# DACWaveyRadar.net
KiCad netlist of a schematic drawn in Altium Designer
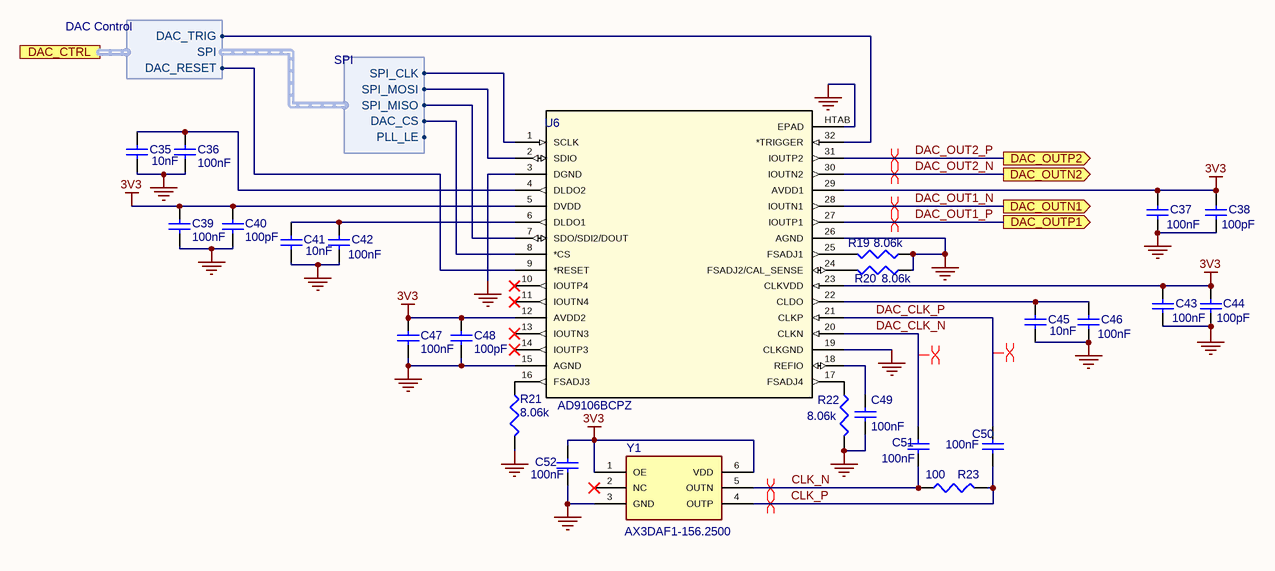
[diagram p0: DACWaveyRadar.SchDoc]

(export (version "E")
  (design (tool "Eeschema 10.0.6"))
  (components
    (comp (ref "C35")
      (value "10nF")
      (footprint "CAPC0402(1005)60_L")
      (description "Chip Capacitor, 10nF +/-20%, 50V, 0402, Thickness 0.6 mm")
      (fields (field (name "TOLERANCE") "5%") (field (name "Comment") "Capacitor 10nF +/-20% 50V 0402"))
      (libsource (lib "University of South Florida") (part "CAP-NP-2"))
    )
    (comp (ref "C36")
      (value "100nF")
      (footprint "CAPC0402(1005)60_L")
      (description "Chip Capacitor, 100nF +/-20%, 10V, 0402, Thickness 0.6 mm")
      (fields (field (name "TOLERANCE") "20%") (field (name "Comment") "Capacitor 100nF +/-20% 10V 0402"))
      (libsource (lib "University of South Florida") (part "CAP-NP-2"))
    )
    (comp (ref "C37")
      (value "100nF")
      (footprint "CAPC0402(1005)60_L")
      (description "Chip Capacitor, 100nF +/-20%, 10V, 0402, Thickness 0.6 mm")
      (fields (field (name "TOLERANCE") "20%") (field (name "Comment") "Capacitor 100nF +/-20% 10V 0402"))
      (libsource (lib "University of South Florida") (part "CAP-NP-2"))
    )
    (comp (ref "C38")
      (value "100pF")
      (footprint "CAPC1005X56X25LL10T15")
      (fields (field (name "Comment") "04023A101JAT2A"))
      (libsource (lib "University of South Florida") (part "CAP-NP-2"))
    )
    (comp (ref "C39")
      (value "100nF")
      (footprint "CAPC0402(1005)60_L")
      (description "Chip Capacitor, 100nF +/-20%, 10V, 0402, Thickness 0.6 mm")
      (fields (field (name "TOLERANCE") "20%") (field (name "Comment") "Capacitor 100nF +/-20% 10V 0402"))
      (libsource (lib "University of South Florida") (part "CAP-NP-2"))
    )
    (comp (ref "C40")
      (value "100pF")
      (footprint "CAPC1005X56X25LL10T15")
      (fields (field (name "Comment") "04023A101JAT2A"))
      (libsource (lib "University of South Florida") (part "CAP-NP-2"))
    )
    (comp (ref "C41")
      (value "10nF")
      (footprint "CAPC0402(1005)60_L")
      (description "Chip Capacitor, 10nF +/-20%, 50V, 0402, Thickness 0.6 mm")
      (fields (field (name "TOLERANCE") "5%") (field (name "Comment") "Capacitor 10nF +/-20% 50V 0402"))
      (libsource (lib "University of South Florida") (part "CAP-NP-2"))
    )
    (comp (ref "C42")
      (value "100nF")
      (footprint "CAPC0402(1005)60_L")
      (description "Chip Capacitor, 100nF +/-20%, 10V, 0402, Thickness 0.6 mm")
      (fields (field (name "TOLERANCE") "20%") (field (name "Comment") "Capacitor 100nF +/-20% 10V 0402"))
      (libsource (lib "University of South Florida") (part "CAP-NP-2"))
    )
    (comp (ref "C43")
      (value "100nF")
      (footprint "CAPC0402(1005)60_L")
      (description "Chip Capacitor, 100nF +/-20%, 10V, 0402, Thickness 0.6 mm")
      (fields (field (name "TOLERANCE") "20%") (field (name "Comment") "Capacitor 100nF +/-20% 10V 0402"))
      (libsource (lib "University of South Florida") (part "CAP-NP-2"))
    )
    (comp (ref "C44")
      (value "100pF")
      (footprint "CAPC1005X56X25LL10T15")
      (fields (field (name "Comment") "04023A101JAT2A"))
      (libsource (lib "University of South Florida") (part "CAP-NP-2"))
    )
    (comp (ref "C45")
      (value "10nF")
      (footprint "CAPC0402(1005)60_L")
      (description "Chip Capacitor, 10nF +/-20%, 50V, 0402, Thickness 0.6 mm")
      (fields (field (name "TOLERANCE") "5%") (field (name "Comment") "Capacitor 10nF +/-20% 50V 0402"))
      (libsource (lib "University of South Florida") (part "CAP-NP-2"))
    )
    (comp (ref "C46")
      (value "100nF")
      (footprint "CAPC0402(1005)60_L")
      (description "Chip Capacitor, 100nF +/-20%, 10V, 0402, Thickness 0.6 mm")
      (fields (field (name "TOLERANCE") "20%") (field (name "Comment") "Capacitor 100nF +/-20% 10V 0402"))
      (libsource (lib "University of South Florida") (part "CAP-NP-2"))
    )
    (comp (ref "C47")
      (value "100nF")
      (footprint "CAPC0402(1005)60_L")
      (description "Chip Capacitor, 100nF +/-20%, 10V, 0402, Thickness 0.6 mm")
      (fields (field (name "TOLERANCE") "20%") (field (name "Comment") "Capacitor 100nF +/-20% 10V 0402"))
      (libsource (lib "University of South Florida") (part "CAP-NP-2"))
    )
    (comp (ref "C48")
      (value "100pF")
      (footprint "CAPC1005X56X25LL10T15")
      (fields (field (name "Comment") "04023A101JAT2A"))
      (libsource (lib "University of South Florida") (part "CAP-NP-2"))
    )
    (comp (ref "C49")
      (value "100nF")
      (footprint "CAPC0402(1005)60_L")
      (description "Chip Capacitor, 100nF +/-20%, 10V, 0402, Thickness 0.6 mm")
      (fields (field (name "TOLERANCE") "20%") (field (name "Comment") "Capacitor 100nF +/-20% 10V 0402"))
      (libsource (lib "University of South Florida") (part "CAP-NP-2"))
    )
    (comp (ref "C50")
      (value "100nF")
      (footprint "CAPC0402(1005)60_L")
      (description "Chip Capacitor, 100nF +/-20%, 10V, 0402, Thickness 0.6 mm")
      (fields (field (name "TOLERANCE") "20%") (field (name "Comment") "Capacitor 100nF +/-20% 10V 0402"))
      (libsource (lib "University of South Florida") (part "CAP-NP-2"))
    )
    (comp (ref "C51")
      (value "100nF")
      (footprint "CAPC0402(1005)60_L")
      (description "Chip Capacitor, 100nF +/-20%, 10V, 0402, Thickness 0.6 mm")
      (fields (field (name "TOLERANCE") "20%") (field (name "Comment") "Capacitor 100nF +/-20% 10V 0402"))
      (libsource (lib "University of South Florida") (part "CAP-NP-2"))
    )
    (comp (ref "C52")
      (value "100nF")
      (footprint "CAPC0402(1005)60_L")
      (description "Chip Capacitor, 100nF +/-20%, 10V, 0402, Thickness 0.6 mm")
      (fields (field (name "TOLERANCE") "20%") (field (name "Comment") "Capacitor 100nF +/-20% 10V 0402"))
      (libsource (lib "University of South Florida") (part "CAP-NP-2"))
    )
    (comp (ref "R19")
      (value "8.06k")
      (footprint "RESC1005X40X25ML05T05")
      (description "Res Thick Film 0402 8.06K Ohm 1% 0.063W(1/16W) ±100ppm/C Molded SMD Automotive Paper T/R")
      (fields (field (name "Comment") "CRCW04028K06FKED"))
      (libsource (lib "University of South Florida") (part "ResistorSymbol"))
    )
    (comp (ref "R20")
      (value "8.06k")
      (footprint "RESC1005X40X25ML05T05")
      (description "Res Thick Film 0402 8.06K Ohm 1% 0.063W(1/16W) ±100ppm/C Molded SMD Automotive Paper T/R")
      (fields (field (name "Comment") "CRCW04028K06FKED"))
      (libsource (lib "University of South Florida") (part "ResistorSymbol"))
    )
    (comp (ref "R21")
      (value "8.06k")
      (footprint "RESC1005X40X25ML05T05")
      (description "Res Thick Film 0402 8.06K Ohm 1% 0.063W(1/16W) ±100ppm/C Molded SMD Automotive Paper T/R")
      (fields (field (name "Comment") "CRCW04028K06FKED"))
      (libsource (lib "University of South Florida") (part "ResistorSymbol"))
    )
    (comp (ref "R22")
      (value "8.06k")
      (footprint "RESC1005X40X25ML05T05")
      (description "Res Thick Film 0402 8.06K Ohm 1% 0.063W(1/16W) ±100ppm/C Molded SMD Automotive Paper T/R")
      (fields (field (name "Comment") "CRCW04028K06FKED"))
      (libsource (lib "University of South Florida") (part "ResistorSymbol"))
    )
    (comp (ref "R23")
      (value "100")
      (footprint "RESC0402(1005)_L")
      (description "Chip Resistor, 100 Ohms, +/-1 %, 63 mW, -55 to 155 degC, 0402")
      (fields (field (name "POWER") "63mW") (field (name "TOLERANCE") "1%"))
      (libsource (lib "University of South Florida") (part "RES-2"))
    )
    (comp (ref "U6")
      (value "AD9106BCPZ")
      (footprint "CP_32_12_ADI")
      (description "No Description Available")
      (fields (field (name "COPYRIGHT") "Copyright (C) 2018 Accelerated Designs. All rights reserved"))
      (libsource (lib "University of South Florida") (part "AD9106BCPZ"))
    )
    (comp (ref "Y1")
      (value "AX3DAF1-156.2500")
      (footprint "AX3DAF1")
      (description "Oscillator XO 156.25MHz ±50ppm LVDS 55% 3.3V 6-Pin SMD Bulk")
      (libsource (lib "University of South Florida") (part "AX3DAF1-156.2500"))
    )
  )
  (nets
    (net (code "5") (name "/CLK_N") (class "Default")
      (node (ref "C51") (pin "2") (pinfunction "2_2") (pintype "passive"))
      (node (ref "R23") (pin "1") (pinfunction "1_1") (pintype "passive"))
      (node (ref "Y1") (pin "5") (pinfunction "OUTN_5") (pintype "passive"))
    )
    (net (code "6") (name "/CLK_P") (class "Default")
      (node (ref "C50") (pin "2") (pinfunction "2_2") (pintype "passive"))
      (node (ref "R23") (pin "2") (pinfunction "2_2") (pintype "passive"))
      (node (ref "Y1") (pin "4") (pinfunction "OUTP_4") (pintype "passive"))
    )
    (net (code "7") (name "/DAC_CLK_N") (class "Default")
      (node (ref "C51") (pin "1") (pinfunction "1_1") (pintype "passive"))
      (node (ref "U6") (pin "20") (pinfunction "CLKN_20") (pintype "input"))
    )
    (net (code "8") (name "/DAC_CLK_P") (class "Default")
      (node (ref "C50") (pin "1") (pinfunction "1_1") (pintype "passive"))
      (node (ref "U6") (pin "21") (pinfunction "CLKP_21") (pintype "input"))
    )
    (net (code "9") (name "/DAC_CS") (class "Default")
      (node (ref "U6") (pin "8") (pinfunction "*CS_8") (pintype "passive"))
    )
    (net (code "11") (name "/DAC_OUT1_N") (class "Default")
      (node (ref "U6") (pin "28") (pinfunction "IOUTN1_28") (pintype "output"))
    )
    (net (code "12") (name "/DAC_OUT1_P") (class "Default")
      (node (ref "U6") (pin "27") (pinfunction "IOUTP1_27") (pintype "output"))
    )
    (net (code "13") (name "/DAC_OUT2_N") (class "Default")
      (node (ref "U6") (pin "30") (pinfunction "IOUTN2_30") (pintype "output"))
    )
    (net (code "14") (name "/DAC_OUT2_P") (class "Default")
      (node (ref "U6") (pin "31") (pinfunction "IOUTP2_31") (pintype "output"))
    )
    (net (code "15") (name "/DAC_RESET") (class "Default")
      (node (ref "U6") (pin "9") (pinfunction "*RESET_9") (pintype "passive"))
    )
    (net (code "16") (name "/DAC_TRIG") (class "Default")
      (node (ref "U6") (pin "32") (pinfunction "*TRIGGER_32") (pintype "input"))
    )
    (net (code "17") (name "/SPI_CLK") (class "Default")
      (node (ref "U6") (pin "1") (pinfunction "SCLK_1") (pintype "input"))
    )
    (net (code "18") (name "/SPI_MISO") (class "Default")
      (node (ref "U6") (pin "7") (pinfunction "SDO/SDI2/DOUT_7") (pintype "bidirectional"))
    )
    (net (code "19") (name "/SPI_MOSI") (class "Default")
      (node (ref "U6") (pin "2") (pinfunction "SDIO_2") (pintype "bidirectional"))
    )
    (net (code "21") (name "3V3") (class "Default")
      (node (ref "C37") (pin "2") (pinfunction "2_2") (pintype "passive"))
      (node (ref "C38") (pin "2") (pinfunction "2_2") (pintype "passive"))
      (node (ref "C39") (pin "1") (pinfunction "1_1") (pintype "passive"))
      (node (ref "C40") (pin "1") (pinfunction "1_1") (pintype "passive"))
      (node (ref "C43") (pin "2") (pinfunction "2_2") (pintype "passive"))
      (node (ref "C44") (pin "2") (pinfunction "2_2") (pintype "passive"))
      (node (ref "C47") (pin "1") (pinfunction "1_1") (pintype "passive"))
      (node (ref "C48") (pin "1") (pinfunction "1_1") (pintype "passive"))
      (node (ref "C52") (pin "1") (pinfunction "1_1") (pintype "passive"))
      (node (ref "U6") (pin "12") (pinfunction "AVDD2_12") (pintype "power_in"))
      (node (ref "U6") (pin "23") (pinfunction "CLKVDD_23") (pintype "input"))
      (node (ref "U6") (pin "29") (pinfunction "AVDD1_29") (pintype "power_in"))
      (node (ref "U6") (pin "5") (pinfunction "DVDD_5") (pintype "power_in"))
      (node (ref "Y1") (pin "1") (pinfunction "OE_1") (pintype "passive"))
      (node (ref "Y1") (pin "6") (pinfunction "VDD_6") (pintype "power_in"))
    )
    (net (code "22") (name "GND") (class "Default")
      (node (ref "C35") (pin "2") (pinfunction "2_2") (pintype "passive"))
      (node (ref "C36") (pin "1") (pinfunction "1_1") (pintype "passive"))
      (node (ref "C37") (pin "1") (pinfunction "1_1") (pintype "passive"))
      (node (ref "C38") (pin "1") (pinfunction "1_1") (pintype "passive"))
      (node (ref "C39") (pin "2") (pinfunction "2_2") (pintype "passive"))
      (node (ref "C40") (pin "2") (pinfunction "2_2") (pintype "passive"))
      (node (ref "C41") (pin "2") (pinfunction "2_2") (pintype "passive"))
      (node (ref "C42") (pin "1") (pinfunction "1_1") (pintype "passive"))
      (node (ref "C43") (pin "1") (pinfunction "1_1") (pintype "passive"))
      (node (ref "C44") (pin "1") (pinfunction "1_1") (pintype "passive"))
      (node (ref "C45") (pin "2") (pinfunction "2_2") (pintype "passive"))
      (node (ref "C46") (pin "1") (pinfunction "1_1") (pintype "passive"))
      (node (ref "C47") (pin "2") (pinfunction "2_2") (pintype "passive"))
      (node (ref "C48") (pin "2") (pinfunction "2_2") (pintype "passive"))
      (node (ref "C49") (pin "2") (pinfunction "2_2") (pintype "passive"))
      (node (ref "C52") (pin "2") (pinfunction "2_2") (pintype "passive"))
      (node (ref "R19") (pin "1") (pinfunction "1_1") (pintype "passive"))
      (node (ref "R20") (pin "1") (pinfunction "1_1") (pintype "passive"))
      (node (ref "R21") (pin "2") (pinfunction "2_2") (pintype "passive"))
      (node (ref "R22") (pin "2") (pinfunction "2_2") (pintype "passive"))
      (node (ref "U6") (pin "15") (pinfunction "AGND_15") (pintype "power_in"))
      (node (ref "U6") (pin "19") (pinfunction "CLKGND_19") (pintype "power_in"))
      (node (ref "U6") (pin "26") (pinfunction "AGND_26") (pintype "power_in"))
      (node (ref "U6") (pin "3") (pinfunction "DGND_3") (pintype "power_in"))
      (node (ref "U6") (pin "HTAB") (pinfunction "EPAD_HTAB") (pintype "passive"))
      (node (ref "Y1") (pin "3") (pinfunction "GND_3") (pintype "power_in"))
    )
    (net (code "23") (name "Net-(U6-CLDO)") (class "Default")
      (node (ref "C45") (pin "1") (pinfunction "1_1") (pintype "passive"))
      (node (ref "C46") (pin "2") (pinfunction "2_2") (pintype "passive"))
      (node (ref "U6") (pin "22") (pinfunction "CLDO_22") (pintype "output"))
    )
    (net (code "24") (name "Net-(U6-DLDO1)") (class "Default")
      (node (ref "C41") (pin "1") (pinfunction "1_1") (pintype "passive"))
      (node (ref "C42") (pin "2") (pinfunction "2_2") (pintype "passive"))
      (node (ref "U6") (pin "6") (pinfunction "DLDO1_6") (pintype "output"))
    )
    (net (code "25") (name "Net-(U6-DLDO2)") (class "Default")
      (node (ref "C35") (pin "1") (pinfunction "1_1") (pintype "passive"))
      (node (ref "C36") (pin "2") (pinfunction "2_2") (pintype "passive"))
      (node (ref "U6") (pin "4") (pinfunction "DLDO2_4") (pintype "output"))
    )
    (net (code "26") (name "Net-(U6-FSADJ1)") (class "Default")
      (node (ref "R19") (pin "2") (pinfunction "2_2") (pintype "passive"))
      (node (ref "U6") (pin "25") (pinfunction "FSADJ1_25") (pintype "output"))
    )
    (net (code "27") (name "Net-(U6-FSADJ2{slash}CAL_SENSE)") (class "Default")
      (node (ref "R20") (pin "2") (pinfunction "2_2") (pintype "passive"))
      (node (ref "U6") (pin "24") (pinfunction "FSADJ2/CAL_SENSE_24") (pintype "bidirectional"))
    )
    (net (code "28") (name "Net-(U6-FSADJ3)") (class "Default")
      (node (ref "R21") (pin "1") (pinfunction "1_1") (pintype "passive"))
      (node (ref "U6") (pin "16") (pinfunction "FSADJ3_16") (pintype "output"))
    )
    (net (code "29") (name "Net-(U6-FSADJ4)") (class "Default")
      (node (ref "R22") (pin "1") (pinfunction "1_1") (pintype "passive"))
      (node (ref "U6") (pin "17") (pinfunction "FSADJ4_17") (pintype "output"))
    )
    (net (code "30") (name "Net-(U6-REFIO)") (class "Default")
      (node (ref "C49") (pin "1") (pinfunction "1_1") (pintype "passive"))
      (node (ref "U6") (pin "18") (pinfunction "REFIO_18") (pintype "bidirectional"))
    )
    (net (code "31") (name "unconnected-(U6-IOUTN3-Pad13)") (class "Default")
      (node (ref "U6") (pin "13") (pinfunction "IOUTN3_13") (pintype "output+no_connect"))
    )
    (net (code "32") (name "unconnected-(U6-IOUTN4-Pad11)") (class "Default")
      (node (ref "U6") (pin "11") (pinfunction "IOUTN4_11") (pintype "output+no_connect"))
    )
    (net (code "33") (name "unconnected-(U6-IOUTP3-Pad14)") (class "Default")
      (node (ref "U6") (pin "14") (pinfunction "IOUTP3_14") (pintype "output+no_connect"))
    )
    (net (code "34") (name "unconnected-(U6-IOUTP4-Pad10)") (class "Default")
      (node (ref "U6") (pin "10") (pinfunction "IOUTP4_10") (pintype "output+no_connect"))
    )
    (net (code "35") (name "unconnected-(Y1-NC-Pad2)") (class "Default")
      (node (ref "Y1") (pin "2") (pinfunction "NC_2") (pintype "passive+no_connect"))
    )
  )
)
